# mcu_board_v1.net
KiCad netlist of a schematic drawn in EAGLE
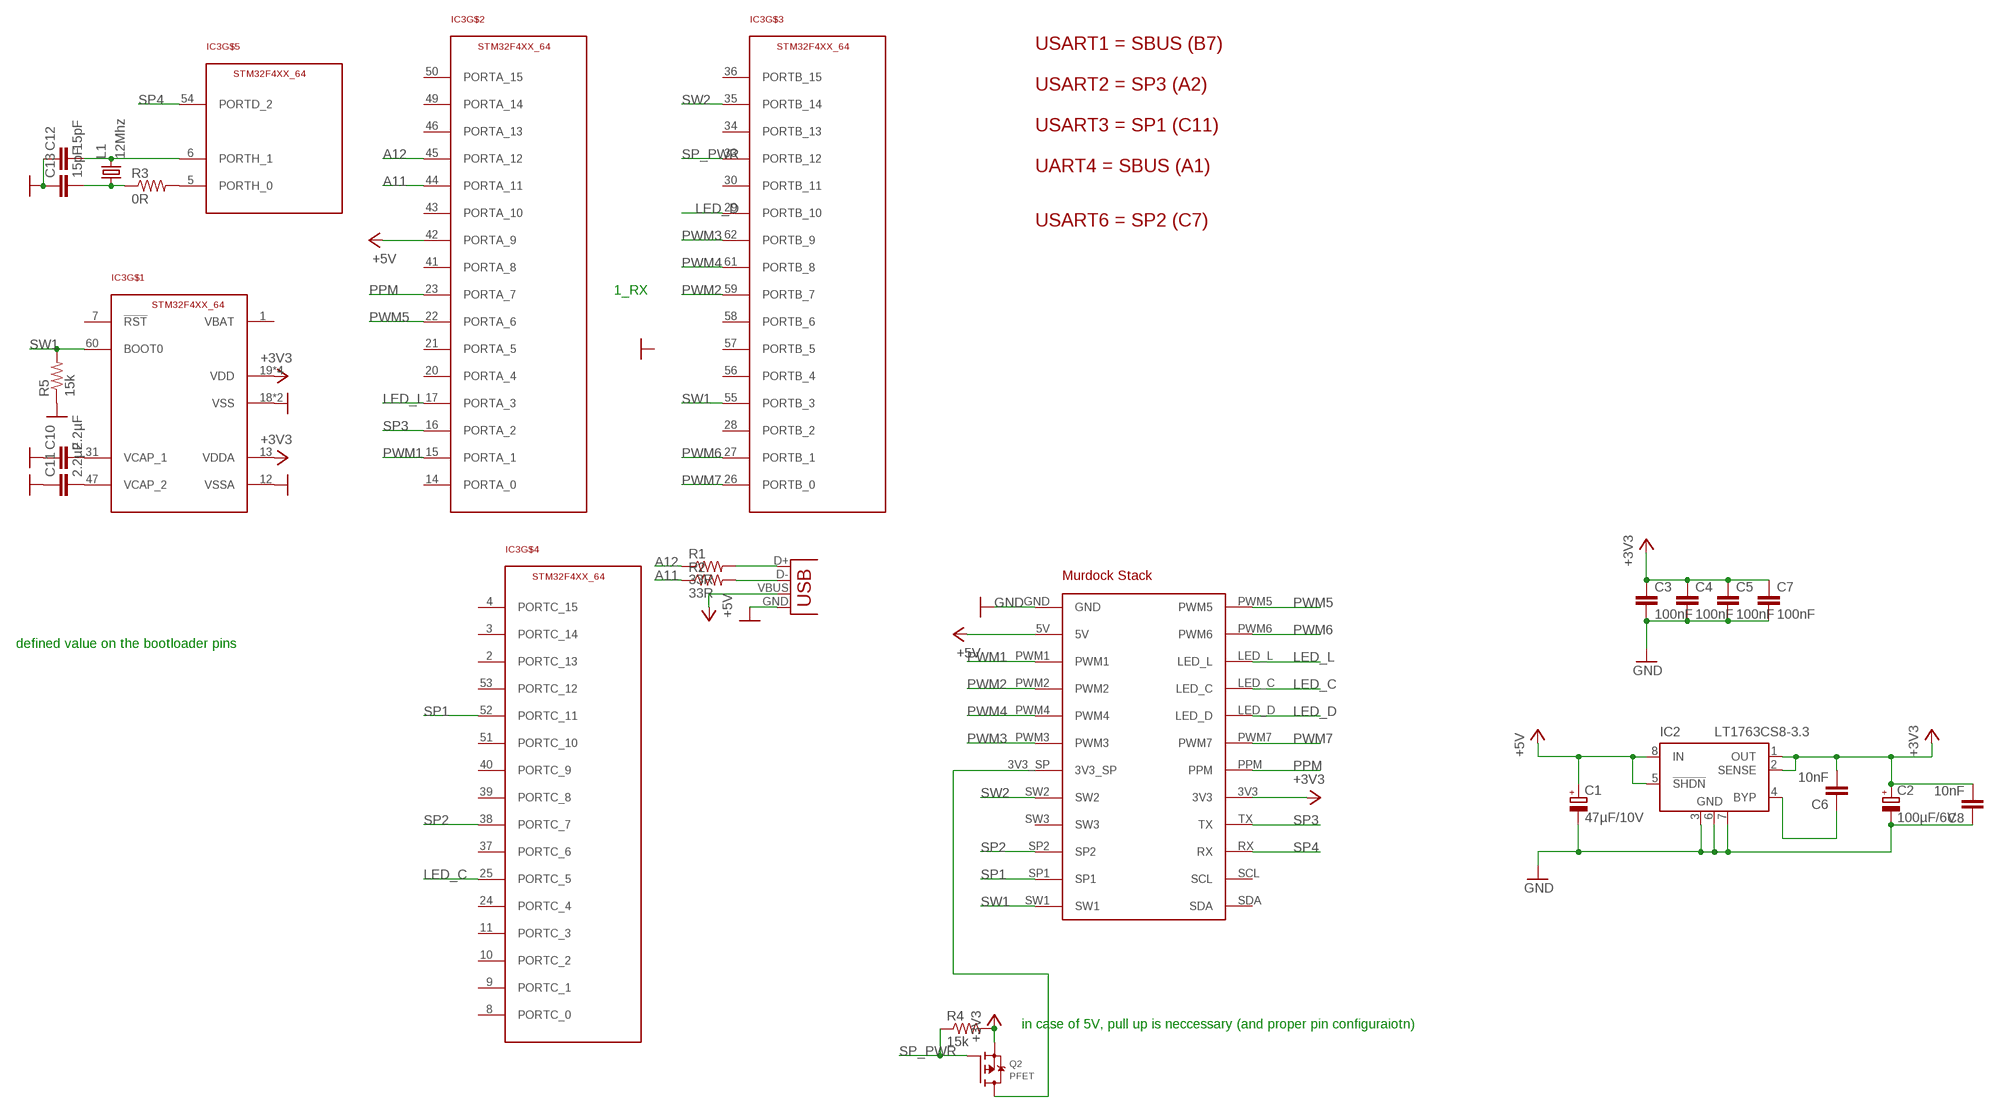
[diagram p0: schematic, sheet 1]

(export (version "E")
  (design (tool "Eeschema 10.0.6"))
  (components
    (comp (ref "C1")
      (value "47µF/10V")
      (footprint "eagle-import:SMC_D")
      (libsource (lib "eagle-import") (part "CPOL-EUSMCD"))
    )
    (comp (ref "C2")
      (value "100µF/6V")
      (footprint "eagle-import:SMC_D")
      (libsource (lib "eagle-import") (part "CPOL-EUSMCD"))
    )
    (comp (ref "C3")
      (value "100nF")
      (footprint "eagle-import:0402-CAP")
      (libsource (lib "eagle-import") (part "CAP0402-CAP"))
    )
    (comp (ref "C4")
      (value "100nF")
      (footprint "eagle-import:0402-CAP")
      (libsource (lib "eagle-import") (part "CAP0402-CAP"))
    )
    (comp (ref "C5")
      (value "100nF")
      (footprint "eagle-import:0402-CAP")
      (libsource (lib "eagle-import") (part "CAP0402-CAP"))
    )
    (comp (ref "C6")
      (value "10nF")
      (footprint "eagle-import:C0402")
      (libsource (lib "eagle-import") (part "C-EUC0402"))
    )
    (comp (ref "C7")
      (value "100nF")
      (footprint "eagle-import:0402-CAP")
      (libsource (lib "eagle-import") (part "CAP0402-CAP"))
    )
    (comp (ref "C8")
      (value "10nF")
      (footprint "eagle-import:C0402")
      (libsource (lib "eagle-import") (part "C-EUC0402"))
    )
    (comp (ref "C10")
      (value "2.2µF")
      (footprint "eagle-import:0805")
      (libsource (lib "eagle-import") (part "CAP0805"))
    )
    (comp (ref "C11")
      (value "2.2µF")
      (footprint "eagle-import:0805")
      (libsource (lib "eagle-import") (part "CAP0805"))
    )
    (comp (ref "C12")
      (value "15pF")
      (footprint "eagle-import:0402-CAP")
      (libsource (lib "eagle-import") (part "CAP0402-CAP"))
    )
    (comp (ref "C13")
      (value "15pF")
      (footprint "eagle-import:0402-CAP")
      (libsource (lib "eagle-import") (part "CAP0402-CAP"))
    )
    (comp (ref "IC2")
      (value "LT1763CS8-3.3")
      (footprint "eagle-import:SOIC8")
      (libsource (lib "eagle-import") (part "LT1763CS8-3.3"))
    )
    (comp (ref "IC3")
      (value "STM32F4XX_64")
      (footprint "eagle-import:TQFP64")
      (libsource (lib "eagle-import") (part "STM32F4XX_64"))
    )
    (comp (ref "L1")
      (value "12Mhz")
      (footprint "eagle-import:X22")
      (libsource (lib "eagle-import") (part "X22-OSCILLATOR"))
    )
    (comp (ref "Q2")
      (value "PFET")
      (footprint "eagle-import:SOT23-R")
      (libsource (lib "eagle-import") (part "MOSFET-P"))
    )
    (comp (ref "R1")
      (value "33R")
      (footprint "eagle-import:0402-RES")
      (libsource (lib "eagle-import") (part "RESISTOR0402-RES"))
    )
    (comp (ref "R2")
      (value "33R")
      (footprint "eagle-import:0402-RES")
      (libsource (lib "eagle-import") (part "RESISTOR0402-RES"))
    )
    (comp (ref "R3")
      (value "0R")
      (footprint "eagle-import:0402-RES")
      (libsource (lib "eagle-import") (part "RESISTOR0402-RES"))
    )
    (comp (ref "R4")
      (value "15k")
      (footprint "eagle-import:0402-RES")
      (libsource (lib "eagle-import") (part "RESISTOR0402-RES"))
    )
    (comp (ref "R5")
      (value "15k")
      (footprint "eagle-import:0402-RES")
      (libsource (lib "eagle-import") (part "RESISTOR0402-RES"))
    )
    (comp (ref "X1")
      (value "USBSMD")
      (footprint "eagle-import:USB-MINIB")
      (libsource (lib "eagle-import") (part "USBSMD"))
    )
    (comp (ref "X2")
      (value "MURDOCK_STACK")
      (footprint "eagle-import:MURDOCK_STACK")
      (libsource (lib "eagle-import") (part "MURDOCK_STACK"))
    )
  )
  (nets
    (net (code "1") (name "+3V3") (class "Default")
      (node (ref "C2") (pin "+") (pinfunction "+_+") (pintype "passive"))
      (node (ref "C3") (pin "1") (pinfunction "1_1") (pintype "passive"))
      (node (ref "C4") (pin "1") (pinfunction "1_1") (pintype "passive"))
      (node (ref "C5") (pin "1") (pinfunction "1_1") (pintype "passive"))
      (node (ref "C6") (pin "2") (pinfunction "2_2") (pintype "passive"))
      (node (ref "C7") (pin "1") (pinfunction "1_1") (pintype "passive"))
      (node (ref "C8") (pin "2") (pinfunction "2_2") (pintype "passive"))
      (node (ref "IC2") (pin "1") (pinfunction "OUT_1") (pintype "passive"))
      (node (ref "IC2") (pin "2") (pinfunction "SENSE_2") (pintype "input"))
      (node (ref "IC3") (pin "13") (pinfunction "VDDA_13") (pintype "bidirectional"))
      (node (ref "IC3") (pin "19") (pinfunction "VDD_19") (pintype "bidirectional"))
      (node (ref "IC3") (pin "32") (pinfunction "VDD_32") (pintype "bidirectional"))
      (node (ref "IC3") (pin "48") (pinfunction "VDD_48") (pintype "bidirectional"))
      (node (ref "IC3") (pin "64") (pinfunction "VDD_64") (pintype "bidirectional"))
      (node (ref "Q2") (pin "2") (pinfunction "S_2") (pintype "passive"))
      (node (ref "R4") (pin "2") (pinfunction "2_2") (pintype "passive"))
      (node (ref "X2") (pin "3V3") (pinfunction "3V3_3V3") (pintype "bidirectional"))
    )
    (net (code "2") (name "+5V") (class "Default")
      (node (ref "C1") (pin "+") (pinfunction "+_+") (pintype "passive"))
      (node (ref "IC2") (pin "5") (pinfunction "~{SHDN}_5") (pintype "input"))
      (node (ref "IC2") (pin "8") (pinfunction "IN_8") (pintype "input"))
      (node (ref "IC3") (pin "42") (pinfunction "PORTA_9_42") (pintype "bidirectional"))
      (node (ref "X1") (pin "VBUS") (pinfunction "VBUS_VBUS") (pintype "bidirectional"))
      (node (ref "X2") (pin "5V") (pinfunction "5V_5V") (pintype "bidirectional"))
    )
    (net (code "3") (name "/A11") (class "Default")
      (node (ref "IC3") (pin "44") (pinfunction "PORTA_11_44") (pintype "bidirectional"))
      (node (ref "R2") (pin "1") (pinfunction "1_1") (pintype "passive"))
    )
    (net (code "4") (name "/A12") (class "Default")
      (node (ref "IC3") (pin "45") (pinfunction "PORTA_12_45") (pintype "bidirectional"))
      (node (ref "R1") (pin "1") (pinfunction "1_1") (pintype "passive"))
    )
    (net (code "5") (name "/LED_C") (class "Default")
      (node (ref "IC3") (pin "25") (pinfunction "PORTC_5_25") (pintype "bidirectional"))
      (node (ref "X2") (pin "LED_C") (pinfunction "LED_C_LED_C") (pintype "bidirectional"))
    )
    (net (code "6") (name "/LED_D") (class "Default")
      (node (ref "IC3") (pin "29") (pinfunction "PORTB_10_29") (pintype "bidirectional"))
      (node (ref "X2") (pin "LED_D") (pinfunction "LED_D_LED_D") (pintype "bidirectional"))
    )
    (net (code "7") (name "/LED_L") (class "Default")
      (node (ref "IC3") (pin "17") (pinfunction "PORTA_3_17") (pintype "bidirectional"))
      (node (ref "X2") (pin "LED_L") (pinfunction "LED_L_LED_L") (pintype "bidirectional"))
    )
    (net (code "8") (name "/PPM") (class "Default")
      (node (ref "IC3") (pin "23") (pinfunction "PORTA_7_23") (pintype "bidirectional"))
      (node (ref "X2") (pin "PPM") (pinfunction "PPM_PPM") (pintype "bidirectional"))
    )
    (net (code "9") (name "/PWM1") (class "Default")
      (node (ref "IC3") (pin "15") (pinfunction "PORTA_1_15") (pintype "bidirectional"))
      (node (ref "X2") (pin "PWM1") (pinfunction "PWM1_PWM1") (pintype "bidirectional"))
    )
    (net (code "10") (name "/PWM2") (class "Default")
      (node (ref "IC3") (pin "59") (pinfunction "PORTB_7_59") (pintype "bidirectional"))
      (node (ref "X2") (pin "PWM2") (pinfunction "PWM2_PWM2") (pintype "bidirectional"))
    )
    (net (code "11") (name "/PWM3") (class "Default")
      (node (ref "IC3") (pin "62") (pinfunction "PORTB_9_62") (pintype "bidirectional"))
      (node (ref "X2") (pin "PWM3") (pinfunction "PWM3_PWM3") (pintype "bidirectional"))
    )
    (net (code "12") (name "/PWM4") (class "Default")
      (node (ref "IC3") (pin "61") (pinfunction "PORTB_8_61") (pintype "bidirectional"))
      (node (ref "X2") (pin "PWM4") (pinfunction "PWM4_PWM4") (pintype "bidirectional"))
    )
    (net (code "13") (name "/PWM5") (class "Default")
      (node (ref "IC3") (pin "22") (pinfunction "PORTA_6_22") (pintype "bidirectional"))
      (node (ref "X2") (pin "PWM5") (pinfunction "PWM5_PWM5") (pintype "bidirectional"))
    )
    (net (code "14") (name "/PWM6") (class "Default")
      (node (ref "IC3") (pin "27") (pinfunction "PORTB_1_27") (pintype "bidirectional"))
      (node (ref "X2") (pin "PWM6") (pinfunction "PWM6_PWM6") (pintype "bidirectional"))
    )
    (net (code "15") (name "/PWM7") (class "Default")
      (node (ref "IC3") (pin "26") (pinfunction "PORTB_0_26") (pintype "bidirectional"))
      (node (ref "X2") (pin "PWM7") (pinfunction "PWM7_PWM7") (pintype "bidirectional"))
    )
    (net (code "16") (name "/SP1") (class "Default")
      (node (ref "IC3") (pin "52") (pinfunction "PORTC_11_52") (pintype "bidirectional"))
      (node (ref "X2") (pin "SP1") (pinfunction "SP1_SP1") (pintype "bidirectional"))
    )
    (net (code "17") (name "/SP2") (class "Default")
      (node (ref "IC3") (pin "38") (pinfunction "PORTC_7_38") (pintype "bidirectional"))
      (node (ref "X2") (pin "SP2") (pinfunction "SP2_SP2") (pintype "bidirectional"))
    )
    (net (code "18") (name "/SP3") (class "Default")
      (node (ref "IC3") (pin "16") (pinfunction "PORTA_2_16") (pintype "bidirectional"))
      (node (ref "X2") (pin "TX") (pinfunction "TX_TX") (pintype "bidirectional"))
    )
    (net (code "19") (name "/SP4") (class "Default")
      (node (ref "IC3") (pin "54") (pinfunction "PORTD_2_54") (pintype "bidirectional"))
      (node (ref "X2") (pin "RX") (pinfunction "RX_RX") (pintype "bidirectional"))
    )
    (net (code "20") (name "/SP_PWR") (class "Default")
      (node (ref "IC3") (pin "33") (pinfunction "PORTB_12_33") (pintype "bidirectional"))
      (node (ref "Q2") (pin "1") (pinfunction "G_1") (pintype "passive"))
      (node (ref "R4") (pin "1") (pinfunction "1_1") (pintype "passive"))
    )
    (net (code "21") (name "/SW1") (class "Default")
      (node (ref "IC3") (pin "55") (pinfunction "PORTB_3_55") (pintype "bidirectional"))
      (node (ref "IC3") (pin "60") (pinfunction "BOOT0_60") (pintype "bidirectional"))
      (node (ref "R5") (pin "2") (pinfunction "2_2") (pintype "passive"))
      (node (ref "X2") (pin "SW1") (pinfunction "SW1_SW1") (pintype "bidirectional"))
    )
    (net (code "22") (name "/SW2") (class "Default")
      (node (ref "IC3") (pin "35") (pinfunction "PORTB_14_35") (pintype "bidirectional"))
      (node (ref "X2") (pin "SW2") (pinfunction "SW2_SW2") (pintype "bidirectional"))
    )
    (net (code "23") (name "GND") (class "Default")
      (node (ref "C1") (pin "-") (pinfunction "-_-") (pintype "passive"))
      (node (ref "C10") (pin "1") (pinfunction "1_1") (pintype "passive"))
      (node (ref "C11") (pin "1") (pinfunction "1_1") (pintype "passive"))
      (node (ref "C12") (pin "1") (pinfunction "1_1") (pintype "passive"))
      (node (ref "C13") (pin "1") (pinfunction "1_1") (pintype "passive"))
      (node (ref "C2") (pin "-") (pinfunction "-_-") (pintype "passive"))
      (node (ref "C3") (pin "2") (pinfunction "2_2") (pintype "passive"))
      (node (ref "C4") (pin "2") (pinfunction "2_2") (pintype "passive"))
      (node (ref "C5") (pin "2") (pinfunction "2_2") (pintype "passive"))
      (node (ref "C7") (pin "2") (pinfunction "2_2") (pintype "passive"))
      (node (ref "C8") (pin "1") (pinfunction "1_1") (pintype "passive"))
      (node (ref "IC2") (pin "3") (pinfunction "GND_3") (pintype "power_in"))
      (node (ref "IC2") (pin "6") (pinfunction "GND_6") (pintype "power_in"))
      (node (ref "IC2") (pin "7") (pinfunction "GND_7") (pintype "power_in"))
      (node (ref "IC3") (pin "12") (pinfunction "VSSA_12") (pintype "bidirectional"))
      (node (ref "IC3") (pin "18") (pinfunction "VSS_18") (pintype "bidirectional"))
      (node (ref "IC3") (pin "63") (pinfunction "VSS_63") (pintype "bidirectional"))
      (node (ref "R5") (pin "1") (pinfunction "1_1") (pintype "passive"))
      (node (ref "X1") (pin "GND") (pinfunction "GND_GND") (pintype "bidirectional"))
      (node (ref "X2") (pin "GND") (pinfunction "GND_GND") (pintype "bidirectional"))
    )
    (net (code "24") (name "Net-(C13-Pad2)") (class "Default")
      (node (ref "C13") (pin "2") (pinfunction "2_2") (pintype "passive"))
      (node (ref "L1") (pin "1") (pinfunction "1_1") (pintype "passive"))
      (node (ref "R3") (pin "1") (pinfunction "1_1") (pintype "passive"))
    )
    (net (code "25") (name "Net-(IC2-BYP)") (class "Default")
      (node (ref "C6") (pin "1") (pinfunction "1_1") (pintype "passive"))
      (node (ref "IC2") (pin "4") (pinfunction "BYP_4") (pintype "input"))
    )
    (net (code "26") (name "Net-(IC3A-VCAP_1)") (class "Default")
      (node (ref "C10") (pin "2") (pinfunction "2_2") (pintype "passive"))
      (node (ref "IC3") (pin "31") (pinfunction "VCAP_1_31") (pintype "bidirectional"))
    )
    (net (code "27") (name "Net-(IC3A-VCAP_2)") (class "Default")
      (node (ref "C11") (pin "2") (pinfunction "2_2") (pintype "passive"))
      (node (ref "IC3") (pin "47") (pinfunction "VCAP_2_47") (pintype "bidirectional"))
    )
    (net (code "28") (name "Net-(IC3E-PORTH_0)") (class "Default")
      (node (ref "IC3") (pin "5") (pinfunction "PORTH_0_5") (pintype "bidirectional"))
      (node (ref "R3") (pin "2") (pinfunction "2_2") (pintype "passive"))
    )
    (net (code "29") (name "Net-(IC3E-PORTH_1)") (class "Default")
      (node (ref "C12") (pin "2") (pinfunction "2_2") (pintype "passive"))
      (node (ref "IC3") (pin "6") (pinfunction "PORTH_1_6") (pintype "bidirectional"))
      (node (ref "L1") (pin "3") (pinfunction "2_3") (pintype "passive"))
    )
    (net (code "30") (name "Net-(Q2-D)") (class "Default")
      (node (ref "Q2") (pin "3") (pinfunction "D_3") (pintype "passive"))
      (node (ref "X2") (pin "3V3_SP") (pinfunction "3V3_SP_3V3_SP") (pintype "bidirectional"))
    )
    (net (code "31") (name "Net-(R1-Pad2)") (class "Default")
      (node (ref "R1") (pin "2") (pinfunction "2_2") (pintype "passive"))
      (node (ref "X1") (pin "D+") (pinfunction "D+_D+") (pintype "bidirectional"))
    )
    (net (code "32") (name "Net-(R2-Pad2)") (class "Default")
      (node (ref "R2") (pin "2") (pinfunction "2_2") (pintype "passive"))
      (node (ref "X1") (pin "D-") (pinfunction "D-_D-") (pintype "bidirectional"))
    )
    (net (code "33") (name "unconnected-(IC3A-VBAT-Pad1)") (class "Default")
      (node (ref "IC3") (pin "1") (pinfunction "VBAT_1") (pintype "bidirectional"))
    )
    (net (code "34") (name "unconnected-(IC3A-~{RST}-Pad7)") (class "Default")
      (node (ref "IC3") (pin "7") (pinfunction "~{RST}_7") (pintype "bidirectional"))
    )
    (net (code "35") (name "unconnected-(IC3B-PORTA_0-Pad14)") (class "Default")
      (node (ref "IC3") (pin "14") (pinfunction "PORTA_0_14") (pintype "bidirectional"))
    )
    (net (code "36") (name "unconnected-(IC3B-PORTA_4-Pad20)") (class "Default")
      (node (ref "IC3") (pin "20") (pinfunction "PORTA_4_20") (pintype "bidirectional"))
    )
    (net (code "37") (name "unconnected-(IC3B-PORTA_5-Pad21)") (class "Default")
      (node (ref "IC3") (pin "21") (pinfunction "PORTA_5_21") (pintype "bidirectional"))
    )
    (net (code "38") (name "unconnected-(IC3B-PORTA_8-Pad41)") (class "Default")
      (node (ref "IC3") (pin "41") (pinfunction "PORTA_8_41") (pintype "bidirectional"))
    )
    (net (code "39") (name "unconnected-(IC3B-PORTA_10-Pad43)") (class "Default")
      (node (ref "IC3") (pin "43") (pinfunction "PORTA_10_43") (pintype "bidirectional"))
    )
    (net (code "40") (name "unconnected-(IC3B-PORTA_13-Pad46)") (class "Default")
      (node (ref "IC3") (pin "46") (pinfunction "PORTA_13_46") (pintype "bidirectional"))
    )
    (net (code "41") (name "unconnected-(IC3B-PORTA_14-Pad49)") (class "Default")
      (node (ref "IC3") (pin "49") (pinfunction "PORTA_14_49") (pintype "bidirectional"))
    )
    (net (code "42") (name "unconnected-(IC3B-PORTA_15-Pad50)") (class "Default")
      (node (ref "IC3") (pin "50") (pinfunction "PORTA_15_50") (pintype "bidirectional"))
    )
    (net (code "43") (name "unconnected-(IC3C-PORTB_2-Pad28)") (class "Default")
      (node (ref "IC3") (pin "28") (pinfunction "PORTB_2_28") (pintype "bidirectional"))
    )
    (net (code "44") (name "unconnected-(IC3C-PORTB_4-Pad56)") (class "Default")
      (node (ref "IC3") (pin "56") (pinfunction "PORTB_4_56") (pintype "bidirectional"))
    )
    (net (code "45") (name "unconnected-(IC3C-PORTB_5-Pad57)") (class "Default")
      (node (ref "IC3") (pin "57") (pinfunction "PORTB_5_57") (pintype "bidirectional"))
    )
    (net (code "46") (name "unconnected-(IC3C-PORTB_6-Pad58)") (class "Default")
      (node (ref "IC3") (pin "58") (pinfunction "PORTB_6_58") (pintype "bidirectional"))
    )
    (net (code "47") (name "unconnected-(IC3C-PORTB_11-Pad30)") (class "Default")
      (node (ref "IC3") (pin "30") (pinfunction "PORTB_11_30") (pintype "bidirectional"))
    )
    (net (code "48") (name "unconnected-(IC3C-PORTB_13-Pad34)") (class "Default")
      (node (ref "IC3") (pin "34") (pinfunction "PORTB_13_34") (pintype "bidirectional"))
    )
    (net (code "49") (name "unconnected-(IC3C-PORTB_15-Pad36)") (class "Default")
      (node (ref "IC3") (pin "36") (pinfunction "PORTB_15_36") (pintype "bidirectional"))
    )
    (net (code "50") (name "unconnected-(IC3D-PORTC_0-Pad8)") (class "Default")
      (node (ref "IC3") (pin "8") (pinfunction "PORTC_0_8") (pintype "bidirectional"))
    )
    (net (code "51") (name "unconnected-(IC3D-PORTC_1-Pad9)") (class "Default")
      (node (ref "IC3") (pin "9") (pinfunction "PORTC_1_9") (pintype "bidirectional"))
    )
    (net (code "52") (name "unconnected-(IC3D-PORTC_2-Pad10)") (class "Default")
      (node (ref "IC3") (pin "10") (pinfunction "PORTC_2_10") (pintype "bidirectional"))
    )
    (net (code "53") (name "unconnected-(IC3D-PORTC_3-Pad11)") (class "Default")
      (node (ref "IC3") (pin "11") (pinfunction "PORTC_3_11") (pintype "bidirectional"))
    )
    (net (code "54") (name "unconnected-(IC3D-PORTC_4-Pad24)") (class "Default")
      (node (ref "IC3") (pin "24") (pinfunction "PORTC_4_24") (pintype "bidirectional"))
    )
    (net (code "55") (name "unconnected-(IC3D-PORTC_6-Pad37)") (class "Default")
      (node (ref "IC3") (pin "37") (pinfunction "PORTC_6_37") (pintype "bidirectional"))
    )
    (net (code "56") (name "unconnected-(IC3D-PORTC_8-Pad39)") (class "Default")
      (node (ref "IC3") (pin "39") (pinfunction "PORTC_8_39") (pintype "bidirectional"))
    )
    (net (code "57") (name "unconnected-(IC3D-PORTC_9-Pad40)") (class "Default")
      (node (ref "IC3") (pin "40") (pinfunction "PORTC_9_40") (pintype "bidirectional"))
    )
    (net (code "58") (name "unconnected-(IC3D-PORTC_10-Pad51)") (class "Default")
      (node (ref "IC3") (pin "51") (pinfunction "PORTC_10_51") (pintype "bidirectional"))
    )
    (net (code "59") (name "unconnected-(IC3D-PORTC_12-Pad53)") (class "Default")
      (node (ref "IC3") (pin "53") (pinfunction "PORTC_12_53") (pintype "bidirectional"))
    )
    (net (code "60") (name "unconnected-(IC3D-PORTC_13-Pad2)") (class "Default")
      (node (ref "IC3") (pin "2") (pinfunction "PORTC_13_2") (pintype "bidirectional"))
    )
    (net (code "61") (name "unconnected-(IC3D-PORTC_14-Pad3)") (class "Default")
      (node (ref "IC3") (pin "3") (pinfunction "PORTC_14_3") (pintype "bidirectional"))
    )
    (net (code "62") (name "unconnected-(IC3D-PORTC_15-Pad4)") (class "Default")
      (node (ref "IC3") (pin "4") (pinfunction "PORTC_15_4") (pintype "bidirectional"))
    )
    (net (code "63") (name "unconnected-(X2-PadSCL)") (class "Default")
      (node (ref "X2") (pin "SCL") (pinfunction "SCL_SCL") (pintype "bidirectional"))
    )
    (net (code "64") (name "unconnected-(X2-PadSDA)") (class "Default")
      (node (ref "X2") (pin "SDA") (pinfunction "SDA_SDA") (pintype "bidirectional"))
    )
    (net (code "65") (name "unconnected-(X2-PadSW3)") (class "Default")
      (node (ref "X2") (pin "SW3") (pinfunction "SW3_SW3") (pintype "bidirectional"))
    )
  )
)
